# Cabin.net
KiCad netlist of a schematic drawn in EAGLE
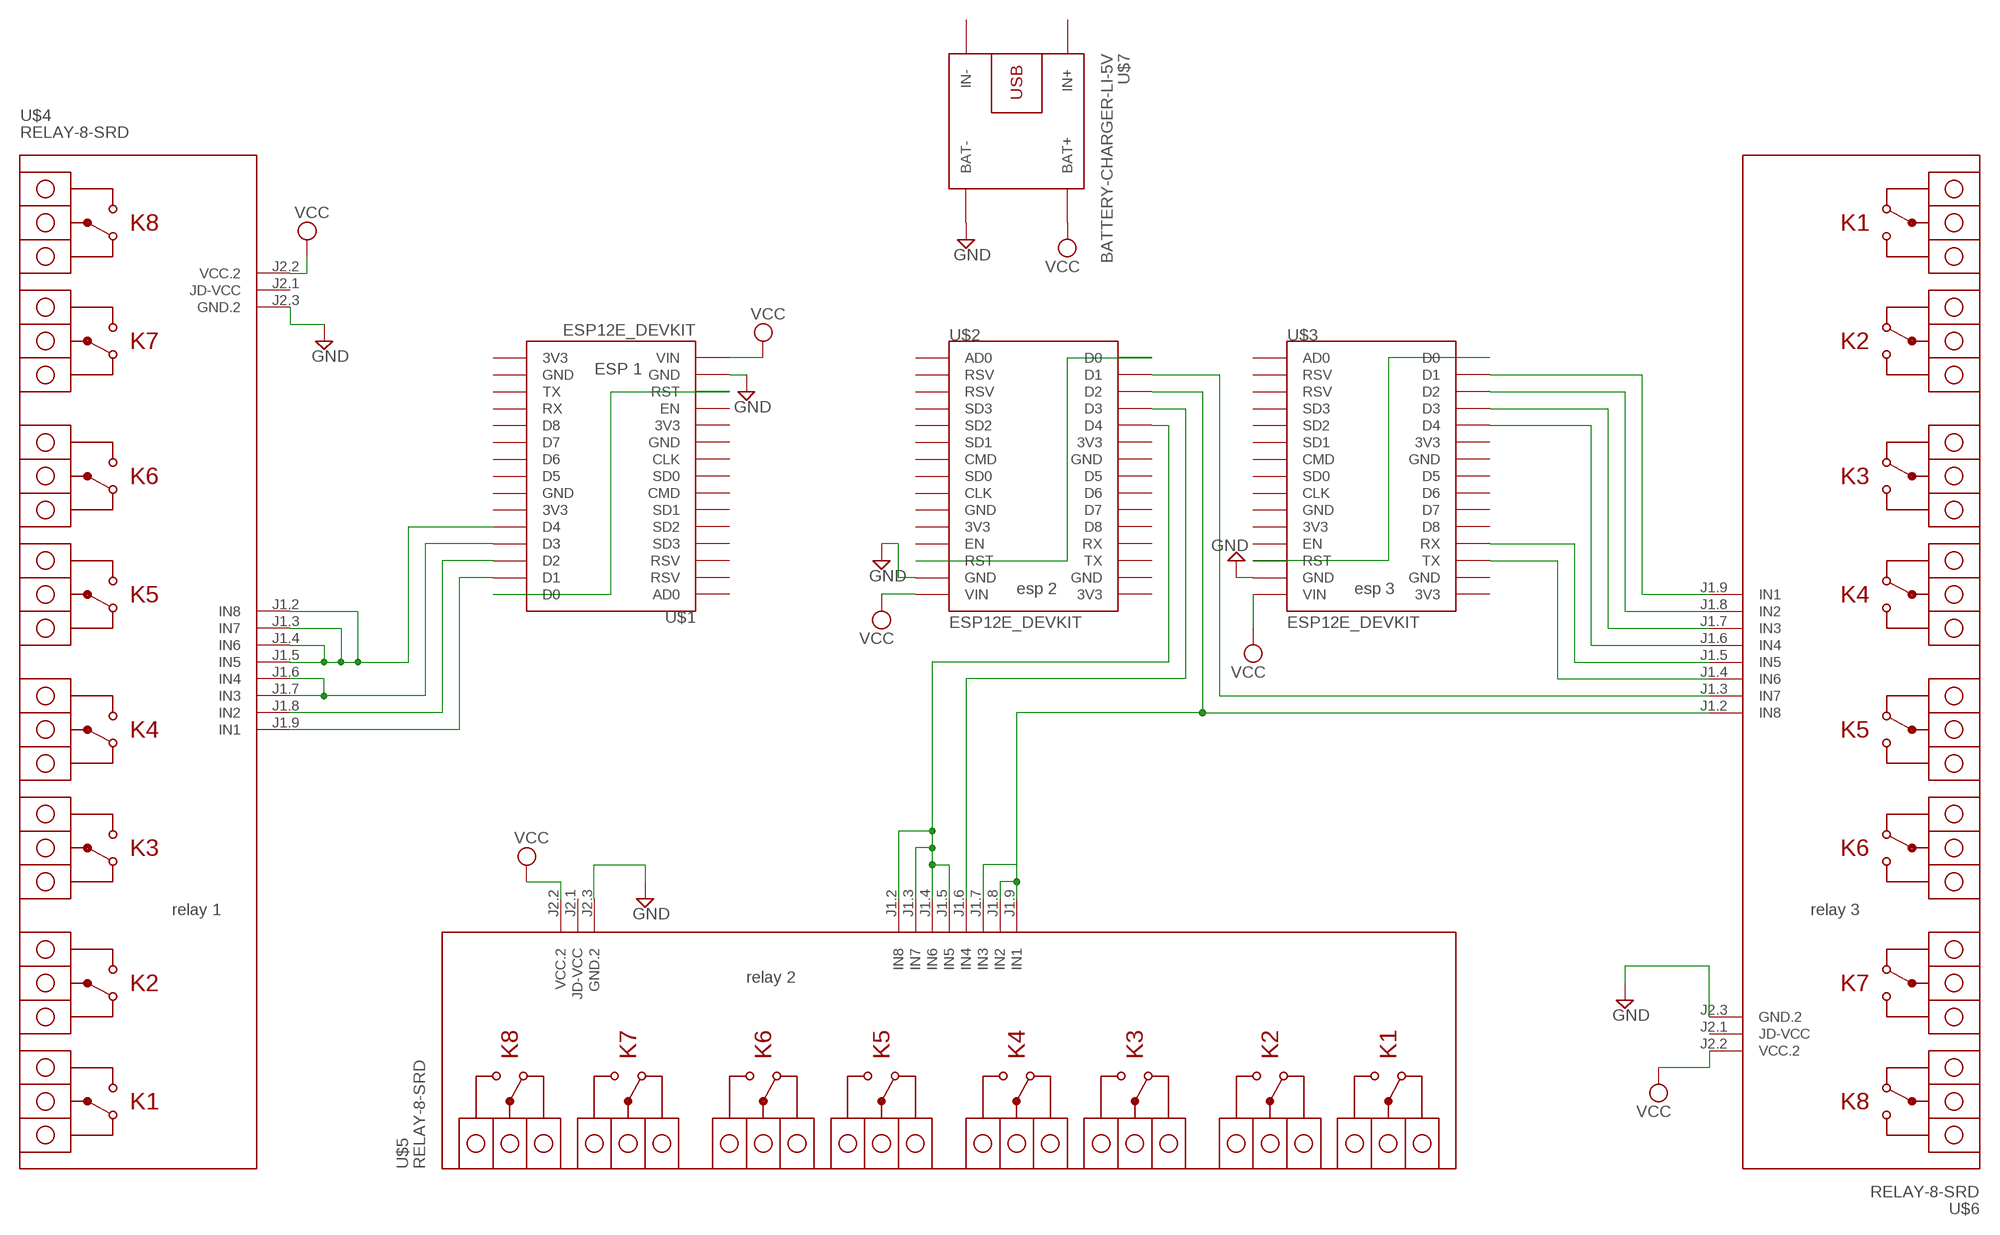
[diagram p0: schematic, sheet 1]

(export (version "E")
  (design (tool "Eeschema 10.0.6"))
  (components
    (comp (ref "U$1")
      (value "ESP12E_DEVKIT")
      (footprint "eagle-import:ESP12E_DEVKIT")
      (libsource (lib "eagle-import") (part "ESP12E_DEVKIT"))
    )
    (comp (ref "U$2")
      (value "ESP12E_DEVKIT")
      (footprint "eagle-import:ESP12E_DEVKIT")
      (libsource (lib "eagle-import") (part "ESP12E_DEVKIT"))
    )
    (comp (ref "U$3")
      (value "ESP12E_DEVKIT")
      (footprint "eagle-import:ESP12E_DEVKIT")
      (libsource (lib "eagle-import") (part "ESP12E_DEVKIT"))
    )
    (comp (ref "U$4")
      (value "RELAY-8-SRD")
      (footprint "eagle-import:RELAY-8-SRD")
      (libsource (lib "eagle-import") (part "RELAY-8-SRD"))
    )
    (comp (ref "U$5")
      (value "RELAY-8-SRD")
      (footprint "eagle-import:RELAY-8-SRD")
      (libsource (lib "eagle-import") (part "RELAY-8-SRD"))
    )
    (comp (ref "U$6")
      (value "RELAY-8-SRD")
      (footprint "eagle-import:RELAY-8-SRD")
      (libsource (lib "eagle-import") (part "RELAY-8-SRD"))
    )
    (comp (ref "U$7")
      (value "BATTERY-CHARGER-LI-5V")
      (footprint "eagle-import:BATTERY-CHARGER-LI-5V")
      (libsource (lib "eagle-import") (part "BATTERY-CHARGER-LI-5V"))
    )
  )
  (nets
    (net (code "1") (name "GND") (class "Default")
      (node (ref "U$1") (pin "GND@1") (pinfunction "GND_GND@1") (pintype "bidirectional"))
      (node (ref "U$2") (pin "GND@1") (pinfunction "GND_GND@1") (pintype "bidirectional"))
      (node (ref "U$3") (pin "GND@1") (pinfunction "GND_GND@1") (pintype "bidirectional"))
      (node (ref "U$4") (pin "J2.3") (pinfunction "GND.2_J2.3") (pintype "power_in"))
      (node (ref "U$5") (pin "J2.3") (pinfunction "GND.2_J2.3") (pintype "power_in"))
      (node (ref "U$6") (pin "J2.3") (pinfunction "GND.2_J2.3") (pintype "power_in"))
      (node (ref "U$7") (pin "BAT-") (pinfunction "BAT-_BAT-") (pintype "bidirectional"))
    )
    (net (code "2") (name "Net-(U$1-PadD0)") (class "Default")
      (node (ref "U$1") (pin "D0") (pinfunction "D0_D0") (pintype "bidirectional"))
      (node (ref "U$1") (pin "RST") (pinfunction "RST_RST") (pintype "bidirectional"))
    )
    (net (code "3") (name "Net-(U$2-PadD0)") (class "Default")
      (node (ref "U$2") (pin "D0") (pinfunction "D0_D0") (pintype "bidirectional"))
      (node (ref "U$2") (pin "RST") (pinfunction "RST_RST") (pintype "bidirectional"))
    )
    (net (code "4") (name "Net-(U$3-PadD0)") (class "Default")
      (node (ref "U$3") (pin "D0") (pinfunction "D0_D0") (pintype "bidirectional"))
      (node (ref "U$3") (pin "RST") (pinfunction "RST_RST") (pintype "bidirectional"))
    )
    (net (code "5") (name "Net-(U$4-IN1)") (class "Default")
      (node (ref "U$1") (pin "D1") (pinfunction "D1_D1") (pintype "bidirectional"))
      (node (ref "U$4") (pin "J1.9") (pinfunction "IN1_J1.9") (pintype "bidirectional"))
    )
    (net (code "6") (name "Net-(U$4-IN2)") (class "Default")
      (node (ref "U$1") (pin "D2") (pinfunction "D2_D2") (pintype "bidirectional"))
      (node (ref "U$4") (pin "J1.8") (pinfunction "IN2_J1.8") (pintype "bidirectional"))
    )
    (net (code "7") (name "Net-(U$4-IN3)") (class "Default")
      (node (ref "U$1") (pin "D3") (pinfunction "D3_D3") (pintype "bidirectional"))
      (node (ref "U$4") (pin "J1.6") (pinfunction "IN4_J1.6") (pintype "bidirectional"))
      (node (ref "U$4") (pin "J1.7") (pinfunction "IN3_J1.7") (pintype "bidirectional"))
    )
    (net (code "8") (name "Net-(U$4-IN5)") (class "Default")
      (node (ref "U$1") (pin "D4") (pinfunction "D4_D4") (pintype "bidirectional"))
      (node (ref "U$4") (pin "J1.2") (pinfunction "IN8_J1.2") (pintype "bidirectional"))
      (node (ref "U$4") (pin "J1.3") (pinfunction "IN7_J1.3") (pintype "bidirectional"))
      (node (ref "U$4") (pin "J1.4") (pinfunction "IN6_J1.4") (pintype "bidirectional"))
      (node (ref "U$4") (pin "J1.5") (pinfunction "IN5_J1.5") (pintype "bidirectional"))
    )
    (net (code "9") (name "Net-(U$5-IN1)") (class "Default")
      (node (ref "U$2") (pin "D2") (pinfunction "D2_D2") (pintype "bidirectional"))
      (node (ref "U$5") (pin "J1.7") (pinfunction "IN3_J1.7") (pintype "bidirectional"))
      (node (ref "U$5") (pin "J1.8") (pinfunction "IN2_J1.8") (pintype "bidirectional"))
      (node (ref "U$5") (pin "J1.9") (pinfunction "IN1_J1.9") (pintype "bidirectional"))
      (node (ref "U$6") (pin "J1.2") (pinfunction "IN8_J1.2") (pintype "bidirectional"))
    )
    (net (code "10") (name "Net-(U$5-IN4)") (class "Default")
      (node (ref "U$2") (pin "D3") (pinfunction "D3_D3") (pintype "bidirectional"))
      (node (ref "U$5") (pin "J1.6") (pinfunction "IN4_J1.6") (pintype "bidirectional"))
    )
    (net (code "11") (name "Net-(U$5-IN5)") (class "Default")
      (node (ref "U$2") (pin "D4") (pinfunction "D4_D4") (pintype "bidirectional"))
      (node (ref "U$5") (pin "J1.2") (pinfunction "IN8_J1.2") (pintype "bidirectional"))
      (node (ref "U$5") (pin "J1.3") (pinfunction "IN7_J1.3") (pintype "bidirectional"))
      (node (ref "U$5") (pin "J1.4") (pinfunction "IN6_J1.4") (pintype "bidirectional"))
      (node (ref "U$5") (pin "J1.5") (pinfunction "IN5_J1.5") (pintype "bidirectional"))
    )
    (net (code "12") (name "Net-(U$6-IN1)") (class "Default")
      (node (ref "U$3") (pin "D1") (pinfunction "D1_D1") (pintype "bidirectional"))
      (node (ref "U$6") (pin "J1.9") (pinfunction "IN1_J1.9") (pintype "bidirectional"))
    )
    (net (code "13") (name "Net-(U$6-IN2)") (class "Default")
      (node (ref "U$3") (pin "D2") (pinfunction "D2_D2") (pintype "bidirectional"))
      (node (ref "U$6") (pin "J1.8") (pinfunction "IN2_J1.8") (pintype "bidirectional"))
    )
    (net (code "14") (name "Net-(U$6-IN3)") (class "Default")
      (node (ref "U$3") (pin "D3") (pinfunction "D3_D3") (pintype "bidirectional"))
      (node (ref "U$6") (pin "J1.7") (pinfunction "IN3_J1.7") (pintype "bidirectional"))
    )
    (net (code "15") (name "Net-(U$6-IN4)") (class "Default")
      (node (ref "U$3") (pin "D4") (pinfunction "D4_D4") (pintype "bidirectional"))
      (node (ref "U$6") (pin "J1.6") (pinfunction "IN4_J1.6") (pintype "bidirectional"))
    )
    (net (code "16") (name "Net-(U$6-IN5)") (class "Default")
      (node (ref "U$3") (pin "RX") (pinfunction "RX_RX") (pintype "bidirectional"))
      (node (ref "U$6") (pin "J1.5") (pinfunction "IN5_J1.5") (pintype "bidirectional"))
    )
    (net (code "17") (name "Net-(U$6-IN6)") (class "Default")
      (node (ref "U$3") (pin "TX") (pinfunction "TX_TX") (pintype "bidirectional"))
      (node (ref "U$6") (pin "J1.4") (pinfunction "IN6_J1.4") (pintype "bidirectional"))
    )
    (net (code "18") (name "Net-(U$6-IN7)") (class "Default")
      (node (ref "U$2") (pin "D1") (pinfunction "D1_D1") (pintype "bidirectional"))
      (node (ref "U$6") (pin "J1.3") (pinfunction "IN7_J1.3") (pintype "bidirectional"))
    )
    (net (code "19") (name "VCC") (class "Default")
      (node (ref "U$1") (pin "VIN") (pinfunction "VIN_VIN") (pintype "bidirectional"))
      (node (ref "U$2") (pin "VIN") (pinfunction "VIN_VIN") (pintype "bidirectional"))
      (node (ref "U$3") (pin "VIN") (pinfunction "VIN_VIN") (pintype "bidirectional"))
      (node (ref "U$4") (pin "J2.2") (pinfunction "VCC.2_J2.2") (pintype "power_in"))
      (node (ref "U$5") (pin "J2.2") (pinfunction "VCC.2_J2.2") (pintype "power_in"))
      (node (ref "U$6") (pin "J2.2") (pinfunction "VCC.2_J2.2") (pintype "power_in"))
      (node (ref "U$7") (pin "BAT+") (pinfunction "BAT+_BAT+") (pintype "bidirectional"))
    )
    (net (code "20") (name "unconnected-(U$1-3V3-Pad3V3@0)") (class "Default")
      (node (ref "U$1") (pin "3V3@0") (pinfunction "3V3_3V3@0") (pintype "bidirectional"))
    )
    (net (code "21") (name "unconnected-(U$1-3V3-Pad3V3@1)") (class "Default")
      (node (ref "U$1") (pin "3V3@1") (pinfunction "3V3_3V3@1") (pintype "bidirectional"))
    )
    (net (code "22") (name "unconnected-(U$1-3V3-Pad3V3@2)") (class "Default")
      (node (ref "U$1") (pin "3V3@2") (pinfunction "3V3_3V3@2") (pintype "bidirectional"))
    )
    (net (code "23") (name "unconnected-(U$1-GND-PadGND@0)") (class "Default")
      (node (ref "U$1") (pin "GND@0") (pinfunction "GND_GND@0") (pintype "bidirectional"))
    )
    (net (code "24") (name "unconnected-(U$1-GND-PadGND@2)") (class "Default")
      (node (ref "U$1") (pin "GND@2") (pinfunction "GND_GND@2") (pintype "bidirectional"))
    )
    (net (code "25") (name "unconnected-(U$1-GND-PadGND@3)") (class "Default")
      (node (ref "U$1") (pin "GND@3") (pinfunction "GND_GND@3") (pintype "bidirectional"))
    )
    (net (code "26") (name "unconnected-(U$1-PadAD0)") (class "Default")
      (node (ref "U$1") (pin "AD0") (pinfunction "AD0_AD0") (pintype "bidirectional"))
    )
    (net (code "27") (name "unconnected-(U$1-PadCLK)") (class "Default")
      (node (ref "U$1") (pin "CLK") (pinfunction "CLK_CLK") (pintype "bidirectional"))
    )
    (net (code "28") (name "unconnected-(U$1-PadCMD)") (class "Default")
      (node (ref "U$1") (pin "CMD") (pinfunction "CMD_CMD") (pintype "bidirectional"))
    )
    (net (code "29") (name "unconnected-(U$1-PadD5)") (class "Default")
      (node (ref "U$1") (pin "D5") (pinfunction "D5_D5") (pintype "bidirectional"))
    )
    (net (code "30") (name "unconnected-(U$1-PadD6)") (class "Default")
      (node (ref "U$1") (pin "D6") (pinfunction "D6_D6") (pintype "bidirectional"))
    )
    (net (code "31") (name "unconnected-(U$1-PadD7)") (class "Default")
      (node (ref "U$1") (pin "D7") (pinfunction "D7_D7") (pintype "bidirectional"))
    )
    (net (code "32") (name "unconnected-(U$1-PadD8)") (class "Default")
      (node (ref "U$1") (pin "D8") (pinfunction "D8_D8") (pintype "bidirectional"))
    )
    (net (code "33") (name "unconnected-(U$1-PadEN)") (class "Default")
      (node (ref "U$1") (pin "EN") (pinfunction "EN_EN") (pintype "bidirectional"))
    )
    (net (code "34") (name "unconnected-(U$1-PadRX)") (class "Default")
      (node (ref "U$1") (pin "RX") (pinfunction "RX_RX") (pintype "bidirectional"))
    )
    (net (code "35") (name "unconnected-(U$1-PadSD0)") (class "Default")
      (node (ref "U$1") (pin "SD0") (pinfunction "SD0_SD0") (pintype "bidirectional"))
    )
    (net (code "36") (name "unconnected-(U$1-PadSD1)") (class "Default")
      (node (ref "U$1") (pin "SD1") (pinfunction "SD1_SD1") (pintype "bidirectional"))
    )
    (net (code "37") (name "unconnected-(U$1-PadSD2)") (class "Default")
      (node (ref "U$1") (pin "SD2") (pinfunction "SD2_SD2") (pintype "bidirectional"))
    )
    (net (code "38") (name "unconnected-(U$1-PadSD3)") (class "Default")
      (node (ref "U$1") (pin "SD3") (pinfunction "SD3_SD3") (pintype "bidirectional"))
    )
    (net (code "39") (name "unconnected-(U$1-PadTX)") (class "Default")
      (node (ref "U$1") (pin "TX") (pinfunction "TX_TX") (pintype "bidirectional"))
    )
    (net (code "40") (name "unconnected-(U$1-RSV-PadRSV@0)") (class "Default")
      (node (ref "U$1") (pin "RSV@0") (pinfunction "RSV_RSV@0") (pintype "bidirectional"))
    )
    (net (code "41") (name "unconnected-(U$1-RSV-PadRSV@1)") (class "Default")
      (node (ref "U$1") (pin "RSV@1") (pinfunction "RSV_RSV@1") (pintype "bidirectional"))
    )
    (net (code "42") (name "unconnected-(U$2-3V3-Pad3V3@0)") (class "Default")
      (node (ref "U$2") (pin "3V3@0") (pinfunction "3V3_3V3@0") (pintype "bidirectional"))
    )
    (net (code "43") (name "unconnected-(U$2-3V3-Pad3V3@1)") (class "Default")
      (node (ref "U$2") (pin "3V3@1") (pinfunction "3V3_3V3@1") (pintype "bidirectional"))
    )
    (net (code "44") (name "unconnected-(U$2-3V3-Pad3V3@2)") (class "Default")
      (node (ref "U$2") (pin "3V3@2") (pinfunction "3V3_3V3@2") (pintype "bidirectional"))
    )
    (net (code "45") (name "unconnected-(U$2-GND-PadGND@0)") (class "Default")
      (node (ref "U$2") (pin "GND@0") (pinfunction "GND_GND@0") (pintype "bidirectional"))
    )
    (net (code "46") (name "unconnected-(U$2-GND-PadGND@2)") (class "Default")
      (node (ref "U$2") (pin "GND@2") (pinfunction "GND_GND@2") (pintype "bidirectional"))
    )
    (net (code "47") (name "unconnected-(U$2-GND-PadGND@3)") (class "Default")
      (node (ref "U$2") (pin "GND@3") (pinfunction "GND_GND@3") (pintype "bidirectional"))
    )
    (net (code "48") (name "unconnected-(U$2-PadAD0)") (class "Default")
      (node (ref "U$2") (pin "AD0") (pinfunction "AD0_AD0") (pintype "bidirectional"))
    )
    (net (code "49") (name "unconnected-(U$2-PadCLK)") (class "Default")
      (node (ref "U$2") (pin "CLK") (pinfunction "CLK_CLK") (pintype "bidirectional"))
    )
    (net (code "50") (name "unconnected-(U$2-PadCMD)") (class "Default")
      (node (ref "U$2") (pin "CMD") (pinfunction "CMD_CMD") (pintype "bidirectional"))
    )
    (net (code "51") (name "unconnected-(U$2-PadD5)") (class "Default")
      (node (ref "U$2") (pin "D5") (pinfunction "D5_D5") (pintype "bidirectional"))
    )
    (net (code "52") (name "unconnected-(U$2-PadD6)") (class "Default")
      (node (ref "U$2") (pin "D6") (pinfunction "D6_D6") (pintype "bidirectional"))
    )
    (net (code "53") (name "unconnected-(U$2-PadD7)") (class "Default")
      (node (ref "U$2") (pin "D7") (pinfunction "D7_D7") (pintype "bidirectional"))
    )
    (net (code "54") (name "unconnected-(U$2-PadD8)") (class "Default")
      (node (ref "U$2") (pin "D8") (pinfunction "D8_D8") (pintype "bidirectional"))
    )
    (net (code "55") (name "unconnected-(U$2-PadEN)") (class "Default")
      (node (ref "U$2") (pin "EN") (pinfunction "EN_EN") (pintype "bidirectional"))
    )
    (net (code "56") (name "unconnected-(U$2-PadRX)") (class "Default")
      (node (ref "U$2") (pin "RX") (pinfunction "RX_RX") (pintype "bidirectional"))
    )
    (net (code "57") (name "unconnected-(U$2-PadSD0)") (class "Default")
      (node (ref "U$2") (pin "SD0") (pinfunction "SD0_SD0") (pintype "bidirectional"))
    )
    (net (code "58") (name "unconnected-(U$2-PadSD1)") (class "Default")
      (node (ref "U$2") (pin "SD1") (pinfunction "SD1_SD1") (pintype "bidirectional"))
    )
    (net (code "59") (name "unconnected-(U$2-PadSD2)") (class "Default")
      (node (ref "U$2") (pin "SD2") (pinfunction "SD2_SD2") (pintype "bidirectional"))
    )
    (net (code "60") (name "unconnected-(U$2-PadSD3)") (class "Default")
      (node (ref "U$2") (pin "SD3") (pinfunction "SD3_SD3") (pintype "bidirectional"))
    )
    (net (code "61") (name "unconnected-(U$2-PadTX)") (class "Default")
      (node (ref "U$2") (pin "TX") (pinfunction "TX_TX") (pintype "bidirectional"))
    )
    (net (code "62") (name "unconnected-(U$2-RSV-PadRSV@0)") (class "Default")
      (node (ref "U$2") (pin "RSV@0") (pinfunction "RSV_RSV@0") (pintype "bidirectional"))
    )
    (net (code "63") (name "unconnected-(U$2-RSV-PadRSV@1)") (class "Default")
      (node (ref "U$2") (pin "RSV@1") (pinfunction "RSV_RSV@1") (pintype "bidirectional"))
    )
    (net (code "64") (name "unconnected-(U$3-3V3-Pad3V3@0)") (class "Default")
      (node (ref "U$3") (pin "3V3@0") (pinfunction "3V3_3V3@0") (pintype "bidirectional"))
    )
    (net (code "65") (name "unconnected-(U$3-3V3-Pad3V3@1)") (class "Default")
      (node (ref "U$3") (pin "3V3@1") (pinfunction "3V3_3V3@1") (pintype "bidirectional"))
    )
    (net (code "66") (name "unconnected-(U$3-3V3-Pad3V3@2)") (class "Default")
      (node (ref "U$3") (pin "3V3@2") (pinfunction "3V3_3V3@2") (pintype "bidirectional"))
    )
    (net (code "67") (name "unconnected-(U$3-GND-PadGND@0)") (class "Default")
      (node (ref "U$3") (pin "GND@0") (pinfunction "GND_GND@0") (pintype "bidirectional"))
    )
    (net (code "68") (name "unconnected-(U$3-GND-PadGND@2)") (class "Default")
      (node (ref "U$3") (pin "GND@2") (pinfunction "GND_GND@2") (pintype "bidirectional"))
    )
    (net (code "69") (name "unconnected-(U$3-GND-PadGND@3)") (class "Default")
      (node (ref "U$3") (pin "GND@3") (pinfunction "GND_GND@3") (pintype "bidirectional"))
    )
    (net (code "70") (name "unconnected-(U$3-PadAD0)") (class "Default")
      (node (ref "U$3") (pin "AD0") (pinfunction "AD0_AD0") (pintype "bidirectional"))
    )
    (net (code "71") (name "unconnected-(U$3-PadCLK)") (class "Default")
      (node (ref "U$3") (pin "CLK") (pinfunction "CLK_CLK") (pintype "bidirectional"))
    )
    (net (code "72") (name "unconnected-(U$3-PadCMD)") (class "Default")
      (node (ref "U$3") (pin "CMD") (pinfunction "CMD_CMD") (pintype "bidirectional"))
    )
    (net (code "73") (name "unconnected-(U$3-PadD5)") (class "Default")
      (node (ref "U$3") (pin "D5") (pinfunction "D5_D5") (pintype "bidirectional"))
    )
    (net (code "74") (name "unconnected-(U$3-PadD6)") (class "Default")
      (node (ref "U$3") (pin "D6") (pinfunction "D6_D6") (pintype "bidirectional"))
    )
    (net (code "75") (name "unconnected-(U$3-PadD7)") (class "Default")
      (node (ref "U$3") (pin "D7") (pinfunction "D7_D7") (pintype "bidirectional"))
    )
    (net (code "76") (name "unconnected-(U$3-PadD8)") (class "Default")
      (node (ref "U$3") (pin "D8") (pinfunction "D8_D8") (pintype "bidirectional"))
    )
    (net (code "77") (name "unconnected-(U$3-PadEN)") (class "Default")
      (node (ref "U$3") (pin "EN") (pinfunction "EN_EN") (pintype "bidirectional"))
    )
    (net (code "78") (name "unconnected-(U$3-PadSD0)") (class "Default")
      (node (ref "U$3") (pin "SD0") (pinfunction "SD0_SD0") (pintype "bidirectional"))
    )
    (net (code "79") (name "unconnected-(U$3-PadSD1)") (class "Default")
      (node (ref "U$3") (pin "SD1") (pinfunction "SD1_SD1") (pintype "bidirectional"))
    )
    (net (code "80") (name "unconnected-(U$3-PadSD2)") (class "Default")
      (node (ref "U$3") (pin "SD2") (pinfunction "SD2_SD2") (pintype "bidirectional"))
    )
    (net (code "81") (name "unconnected-(U$3-PadSD3)") (class "Default")
      (node (ref "U$3") (pin "SD3") (pinfunction "SD3_SD3") (pintype "bidirectional"))
    )
    (net (code "82") (name "unconnected-(U$3-RSV-PadRSV@0)") (class "Default")
      (node (ref "U$3") (pin "RSV@0") (pinfunction "RSV_RSV@0") (pintype "bidirectional"))
    )
    (net (code "83") (name "unconnected-(U$3-RSV-PadRSV@1)") (class "Default")
      (node (ref "U$3") (pin "RSV@1") (pinfunction "RSV_RSV@1") (pintype "bidirectional"))
    )
    (net (code "84") (name "unconnected-(U$4-JD-VCC-PadJ2.1)") (class "Default")
      (node (ref "U$4") (pin "J2.1") (pinfunction "JD-VCC_J2.1") (pintype "bidirectional"))
    )
    (net (code "85") (name "unconnected-(U$5-JD-VCC-PadJ2.1)") (class "Default")
      (node (ref "U$5") (pin "J2.1") (pinfunction "JD-VCC_J2.1") (pintype "bidirectional"))
    )
    (net (code "86") (name "unconnected-(U$6-JD-VCC-PadJ2.1)") (class "Default")
      (node (ref "U$6") (pin "J2.1") (pinfunction "JD-VCC_J2.1") (pintype "bidirectional"))
    )
    (net (code "87") (name "unconnected-(U$7-PadIN+)") (class "Default")
      (node (ref "U$7") (pin "IN+") (pinfunction "IN+_IN+") (pintype "bidirectional"))
    )
    (net (code "88") (name "unconnected-(U$7-PadIN-)") (class "Default")
      (node (ref "U$7") (pin "IN-") (pinfunction "IN-_IN-") (pintype "bidirectional"))
    )
  )
)
